# 1_-_Connectors.net
KiCad netlist of a schematic drawn in Altium Designer
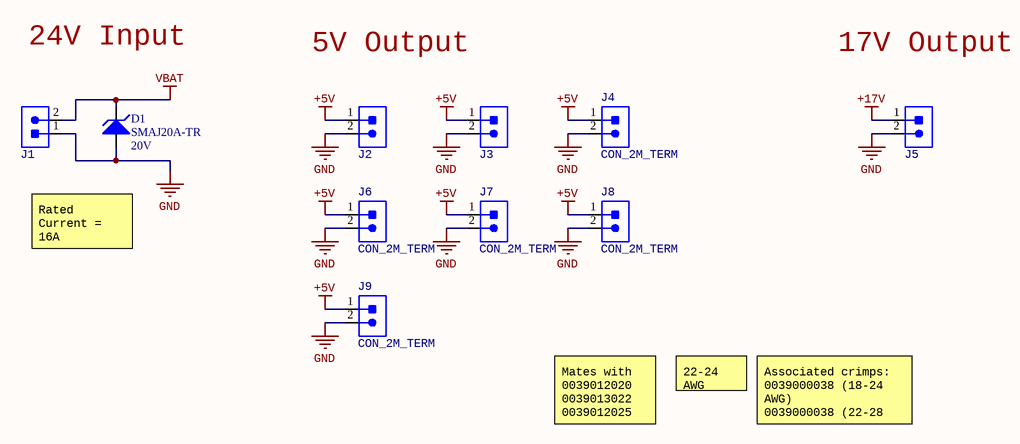
[diagram p0: 1 - Connectors.SchDoc]

(export (version "E")
  (design (tool "Eeschema 10.0.6"))
  (components
    (comp (ref "D1")
      (value "SMAJ20A-TR")
      (footprint "DO-214AC_UNI")
      (description "TVS DIODE, 400W, 20V, DO-214AC (SMA)")
      (fields
        (field (name "MANUFACTURER PART NUMBER 1") "SMAJ20A-TR")
        (field (name "REVERSE STANDOFF VOLTAGE") "20V")
      )
      (libsource (lib "UWRT_Schematic_Library_2020") (part "SMAJ20A-TR"))
    )
    (comp (ref "J1")
      (value "CON_2M_TERM")
      (footprint "1935161")
      (description "TERM BLK 2POS SIDE ENTRY 5MM")
      (fields (field (name "VOLTAGE") "300V"))
      (libsource (lib "UWRT_Schematic_Library_2020") (part "CON_2M_TERM"))
    )
    (comp (ref "J2")
      (value "CON_2M_TERM")
      (footprint "1935161")
      (description "TERM BLK 2POS SIDE ENTRY 5MM")
      (fields (field (name "VOLTAGE") "300V"))
      (libsource (lib "") (part "CON_2M_TERM_1"))
    )
    (comp (ref "J3")
      (value "CON_2M_TERM")
      (footprint "1935161")
      (description "TERM BLK 2POS SIDE ENTRY 5MM")
      (fields (field (name "VOLTAGE") "300V"))
      (libsource (lib "") (part "CON_2M_TERM_1"))
    )
    (comp (ref "J4")
      (value "CON_2M_TERM")
      (footprint "1935161")
      (description "TERM BLK 2POS SIDE ENTRY 5MM")
      (fields (field (name "VOLTAGE") "300V"))
      (libsource (lib "") (part "CON_2M_TERM_1"))
    )
    (comp (ref "J5")
      (value "CON_2M_TERM")
      (footprint "1935161")
      (description "TERM BLK 2POS SIDE ENTRY 5MM")
      (fields (field (name "VOLTAGE") "300V"))
      (libsource (lib "") (part "CON_2M_TERM_1"))
    )
    (comp (ref "J6")
      (value "CON_2M_TERM")
      (footprint "1935161")
      (description "TERM BLK 2POS SIDE ENTRY 5MM")
      (fields (field (name "VOLTAGE") "300V"))
      (libsource (lib "") (part "CON_2M_TERM_1"))
    )
    (comp (ref "J7")
      (value "CON_2M_TERM")
      (footprint "1935161")
      (description "TERM BLK 2POS SIDE ENTRY 5MM")
      (fields (field (name "VOLTAGE") "300V"))
      (libsource (lib "") (part "CON_2M_TERM_1"))
    )
    (comp (ref "J8")
      (value "CON_2M_TERM")
      (footprint "1935161")
      (description "TERM BLK 2POS SIDE ENTRY 5MM")
      (fields (field (name "VOLTAGE") "300V"))
      (libsource (lib "") (part "CON_2M_TERM_1"))
    )
    (comp (ref "J9")
      (value "CON_2M_TERM")
      (footprint "1935161")
      (description "TERM BLK 2POS SIDE ENTRY 5MM")
      (fields (field (name "VOLTAGE") "300V"))
      (libsource (lib "") (part "CON_2M_TERM_1"))
    )
  )
  (nets
    (net (code "1") (name "+5V") (class "Default")
      (node (ref "J2") (pin "1") (pinfunction "1_1") (pintype "passive"))
      (node (ref "J3") (pin "1") (pinfunction "1_1") (pintype "passive"))
      (node (ref "J4") (pin "1") (pinfunction "1_1") (pintype "passive"))
      (node (ref "J6") (pin "1") (pinfunction "1_1") (pintype "passive"))
      (node (ref "J7") (pin "1") (pinfunction "1_1") (pintype "passive"))
      (node (ref "J8") (pin "1") (pinfunction "1_1") (pintype "passive"))
      (node (ref "J9") (pin "1") (pinfunction "1_1") (pintype "passive"))
    )
    (net (code "2") (name "+17V") (class "Default")
      (node (ref "J5") (pin "1") (pinfunction "1_1") (pintype "passive"))
    )
    (net (code "3") (name "GND") (class "Default")
      (node (ref "D1") (pin "1") (pinfunction "1_1") (pintype "passive"))
      (node (ref "J1") (pin "1") (pinfunction "1_1") (pintype "passive"))
      (node (ref "J2") (pin "2") (pinfunction "2_2") (pintype "passive"))
      (node (ref "J3") (pin "2") (pinfunction "2_2") (pintype "passive"))
      (node (ref "J4") (pin "2") (pinfunction "2_2") (pintype "passive"))
      (node (ref "J5") (pin "2") (pinfunction "2_2") (pintype "passive"))
      (node (ref "J6") (pin "2") (pinfunction "2_2") (pintype "passive"))
      (node (ref "J7") (pin "2") (pinfunction "2_2") (pintype "passive"))
      (node (ref "J8") (pin "2") (pinfunction "2_2") (pintype "passive"))
      (node (ref "J9") (pin "2") (pinfunction "2_2") (pintype "passive"))
    )
    (net (code "4") (name "VBAT") (class "Default")
      (node (ref "D1") (pin "2") (pinfunction "2_2") (pintype "passive"))
      (node (ref "J1") (pin "2") (pinfunction "2_2") (pintype "passive"))
    )
  )
)
